# v0_3.net
KiCad netlist of a schematic drawn in EAGLE
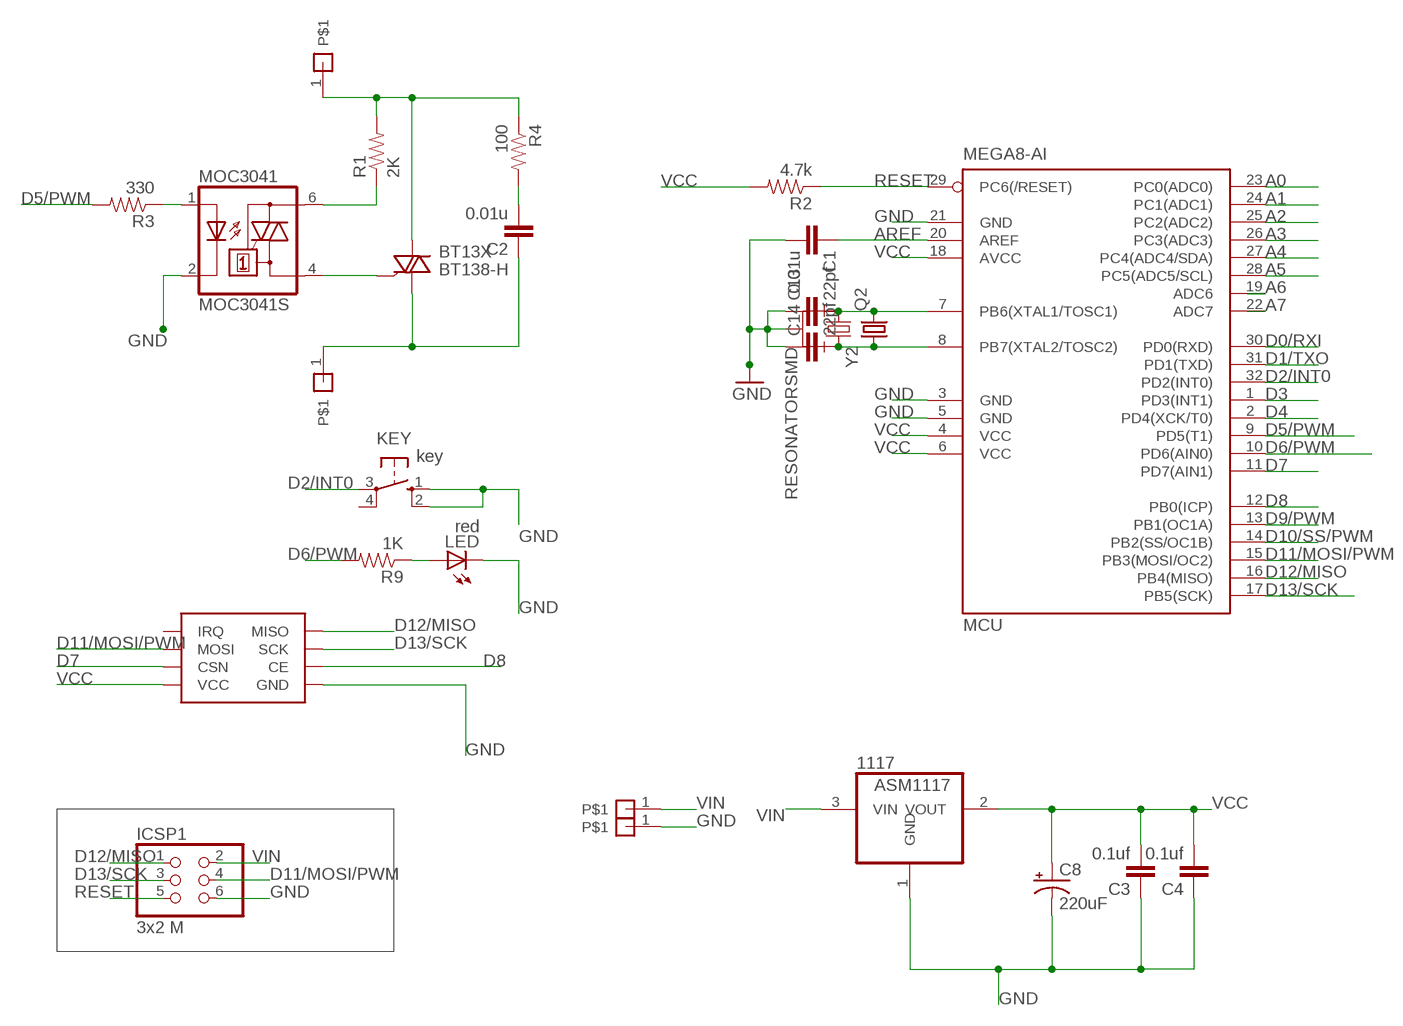
[diagram p0: schematic, sheet 1]

(export (version "E")
  (design (tool "Eeschema 10.0.6"))
  (components
    (comp (ref "1117")
      (value "ASM1117")
      (footprint "eagle-import:SOT223")
      (fields (field (name "MPN") "REG1117"))
      (libsource (lib "eagle-import") (part "REG1117"))
    )
    (comp (ref "BT13X")
      (value "BT138-H")
      (footprint "eagle-import:TO220BH")
      (libsource (lib "eagle-import") (part "BT138-H"))
    )
    (comp (ref "C1")
      (value "0.01u")
      (footprint "eagle-import:0603-CAP")
      (libsource (lib "eagle-import") (part "MY2_CAP0603-CAP"))
    )
    (comp (ref "C2")
      (value "0.01u")
      (footprint "eagle-import:C050-024X044")
      (libsource (lib "eagle-import") (part "C-EU050-024X044"))
    )
    (comp (ref "C3")
      (value "0.1uf")
      (footprint "eagle-import:0603-CAP")
      (libsource (lib "eagle-import") (part "MY_CAP0603-CAP"))
    )
    (comp (ref "C4")
      (value "0.1uf")
      (footprint "eagle-import:0603-CAP")
      (libsource (lib "eagle-import") (part "MY_CAP0603-CAP"))
    )
    (comp (ref "C8")
      (value "220uF")
      (footprint "eagle-import:EIA3528")
      (libsource (lib "eagle-import") (part "CAP_POL3528"))
    )
    (comp (ref "C13")
      (value "22pf")
      (footprint "eagle-import:0603-CAP")
      (libsource (lib "eagle-import") (part "CAP0603-CAP"))
    )
    (comp (ref "C14")
      (value "22pf")
      (footprint "eagle-import:0603-CAP")
      (libsource (lib "eagle-import") (part "CAP0603-CAP"))
    )
    (comp (ref "ICSP1")
      (value "3x2 M")
      (footprint "eagle-import:2X03")
      (libsource (lib "eagle-import") (part "PINHD-2X3"))
    )
    (comp (ref "KEY")
      (value "key")
      (footprint "eagle-import:B3F-10XX")
      (fields
        (field (name "MPN") "B3F-1000")
        (field (name "MPN_1") "B3F-1000")
        (field (name "OC_FARNELL") "176432")
        (field (name "OC_NEWARK") "36M3542")
      )
      (libsource (lib "eagle-import") (part "10-XX"))
    )
    (comp (ref "LED")
      (value "red")
      (footprint "eagle-import:LED3MM")
      (libsource (lib "eagle-import") (part "LED3MM"))
    )
    (comp (ref "MCU")
      (value "MEGA8-AI")
      (footprint "eagle-import:TQFP32-08")
      (fields (field (name "MPN") "ATMEGA8-16AU"))
      (libsource (lib "eagle-import") (part "MEGA8-AI"))
    )
    (comp (ref "MOC3041")
      (value "MOC3041S")
      (footprint "eagle-import:DIL6-SMD")
      (fields
        (field (name "MF") "FAIRCHILD SEMICONDUCTOR")
        (field (name "MPN") "MOC3041S-M")
        (field (name "MF_1") "FAIRCHILD SEMICONDUCTOR")
        (field (name "MPN_1") "MOC3041S-M")
        (field (name "OC_NEWARK") "05C2885")
      )
      (libsource (lib "eagle-import") (part "MOC30S41"))
    )
    (comp (ref "Q2")
      (value "CRYSTALHC49S")
      (footprint "eagle-import:HC49_S")
      (libsource (lib "eagle-import") (part "CRYSTALHC49S"))
    )
    (comp (ref "R1")
      (value "2K")
      (footprint "eagle-import:1206")
      (libsource (lib "eagle-import") (part "MY3_RESISTOR1206"))
    )
    (comp (ref "R2")
      (value "4.7k")
      (footprint "eagle-import:0603-RES")
      (libsource (lib "eagle-import") (part "RESISTOR0603-RES"))
    )
    (comp (ref "R3")
      (value "330")
      (footprint "eagle-import:0603-RES")
      (libsource (lib "eagle-import") (part "RESISTOR0603-RES"))
    )
    (comp (ref "R4")
      (value "100")
      (footprint "eagle-import:1206")
      (libsource (lib "eagle-import") (part "MY3_RESISTOR1206"))
    )
    (comp (ref "R9")
      (value "1K")
      (footprint "eagle-import:0603-RES")
      (libsource (lib "eagle-import") (part "RESISTOR0603-RES"))
    )
    (comp (ref "U$1")
      (value "PIN1")
      (footprint "eagle-import:PIN1")
      (libsource (lib "eagle-import") (part "PIN1"))
    )
    (comp (ref "U$2")
      (value "PIN1")
      (footprint "eagle-import:PIN1")
      (libsource (lib "eagle-import") (part "PIN1"))
    )
    (comp (ref "U$3")
      (value "PIN1")
      (footprint "eagle-import:PIN1")
      (libsource (lib "eagle-import") (part "PIN1"))
    )
    (comp (ref "U$4")
      (value "PIN1")
      (footprint "eagle-import:PIN1")
      (libsource (lib "eagle-import") (part "PIN1"))
    )
    (comp (ref "U$6")
      (value "NRF")
      (footprint "eagle-import:NRF")
      (libsource (lib "eagle-import") (part "NRF"))
    )
    (comp (ref "Y2")
      (value "RESONATORSMD")
      (footprint "eagle-import:RESONATOR-SMD")
      (libsource (lib "eagle-import") (part "RESONATORSMD"))
    )
  )
  (nets
    (net (code "1") (name "/A0") (class "Default")
      (node (ref "MCU") (pin "23") (pinfunction "PC0(ADC0)_23") (pintype "bidirectional"))
    )
    (net (code "2") (name "/A1") (class "Default")
      (node (ref "MCU") (pin "24") (pinfunction "PC1(ADC1)_24") (pintype "bidirectional"))
    )
    (net (code "3") (name "/A2") (class "Default")
      (node (ref "MCU") (pin "25") (pinfunction "PC2(ADC2)_25") (pintype "bidirectional"))
    )
    (net (code "4") (name "/A3") (class "Default")
      (node (ref "MCU") (pin "26") (pinfunction "PC3(ADC3)_26") (pintype "bidirectional"))
    )
    (net (code "5") (name "/A4") (class "Default")
      (node (ref "MCU") (pin "27") (pinfunction "PC4(ADC4/SDA)_27") (pintype "bidirectional"))
    )
    (net (code "6") (name "/A5") (class "Default")
      (node (ref "MCU") (pin "28") (pinfunction "PC5(ADC5/SCL)_28") (pintype "bidirectional"))
    )
    (net (code "7") (name "/A6") (class "Default")
      (node (ref "MCU") (pin "19") (pinfunction "ADC6_19") (pintype "bidirectional"))
    )
    (net (code "8") (name "/A7") (class "Default")
      (node (ref "MCU") (pin "22") (pinfunction "ADC7_22") (pintype "bidirectional"))
    )
    (net (code "9") (name "/AREF") (class "Default")
      (node (ref "C1") (pin "1") (pinfunction "1_1") (pintype "passive"))
      (node (ref "MCU") (pin "20") (pinfunction "AREF_20") (pintype "passive"))
    )
    (net (code "10") (name "/D0{slash}RXI") (class "Default")
      (node (ref "MCU") (pin "30") (pinfunction "PD0(RXD)_30") (pintype "bidirectional"))
    )
    (net (code "11") (name "/D1{slash}TXO") (class "Default")
      (node (ref "MCU") (pin "31") (pinfunction "PD1(TXD)_31") (pintype "bidirectional"))
    )
    (net (code "12") (name "/D2{slash}INT0") (class "Default")
      (node (ref "KEY") (pin "3") (pinfunction "P_3") (pintype "passive"))
      (node (ref "MCU") (pin "32") (pinfunction "PD2(INT0)_32") (pintype "bidirectional"))
    )
    (net (code "13") (name "/D3") (class "Default")
      (node (ref "MCU") (pin "1") (pinfunction "PD3(INT1)_1") (pintype "bidirectional"))
    )
    (net (code "14") (name "/D4") (class "Default")
      (node (ref "MCU") (pin "2") (pinfunction "PD4(XCK/T0)_2") (pintype "bidirectional"))
    )
    (net (code "15") (name "/D5{slash}PWM") (class "Default")
      (node (ref "MCU") (pin "9") (pinfunction "PD5(T1)_9") (pintype "bidirectional"))
      (node (ref "R3") (pin "2") (pinfunction "2_2") (pintype "passive"))
    )
    (net (code "16") (name "/D6{slash}PWM") (class "Default")
      (node (ref "MCU") (pin "10") (pinfunction "PD6(AIN0)_10") (pintype "bidirectional"))
      (node (ref "R9") (pin "2") (pinfunction "2_2") (pintype "passive"))
    )
    (net (code "17") (name "/D7") (class "Default")
      (node (ref "MCU") (pin "11") (pinfunction "PD7(AIN1)_11") (pintype "bidirectional"))
      (node (ref "U$6") (pin "P$4") (pinfunction "CSN_P$4") (pintype "bidirectional"))
    )
    (net (code "18") (name "/D8") (class "Default")
      (node (ref "MCU") (pin "12") (pinfunction "PB0(ICP)_12") (pintype "bidirectional"))
      (node (ref "U$6") (pin "P$3") (pinfunction "CE_P$3") (pintype "bidirectional"))
    )
    (net (code "19") (name "/D9{slash}PWM") (class "Default")
      (node (ref "MCU") (pin "13") (pinfunction "PB1(OC1A)_13") (pintype "bidirectional"))
    )
    (net (code "20") (name "/D10{slash}SS{slash}PWM") (class "Default")
      (node (ref "MCU") (pin "14") (pinfunction "PB2(SS/OC1B)_14") (pintype "bidirectional"))
    )
    (net (code "21") (name "/D11{slash}MOSI{slash}PWM") (class "Default")
      (node (ref "ICSP1") (pin "4") (pinfunction "4_4") (pintype "passive"))
      (node (ref "MCU") (pin "15") (pinfunction "PB3(MOSI/OC2)_15") (pintype "bidirectional"))
      (node (ref "U$6") (pin "P$6") (pinfunction "MOSI_P$6") (pintype "bidirectional"))
    )
    (net (code "22") (name "/D12{slash}MISO") (class "Default")
      (node (ref "ICSP1") (pin "1") (pinfunction "1_1") (pintype "passive"))
      (node (ref "MCU") (pin "16") (pinfunction "PB4(MISO)_16") (pintype "bidirectional"))
      (node (ref "U$6") (pin "P$7") (pinfunction "MISO_P$7") (pintype "bidirectional"))
    )
    (net (code "23") (name "/D13{slash}SCK") (class "Default")
      (node (ref "ICSP1") (pin "3") (pinfunction "3_3") (pintype "passive"))
      (node (ref "MCU") (pin "17") (pinfunction "PB5(SCK)_17") (pintype "bidirectional"))
      (node (ref "U$6") (pin "P$5") (pinfunction "SCK_P$5") (pintype "bidirectional"))
    )
    (net (code "24") (name "/RESET") (class "Default")
      (node (ref "ICSP1") (pin "5") (pinfunction "5_5") (pintype "passive"))
      (node (ref "MCU") (pin "29") (pinfunction "PC6(/RESET)_29") (pintype "bidirectional"))
      (node (ref "R2") (pin "1") (pinfunction "1_1") (pintype "passive"))
    )
    (net (code "25") (name "/VCC") (class "Default")
      (node (ref "1117") (pin "2") (pinfunction "VOUT_2") (pintype "output"))
      (node (ref "C3") (pin "2") (pinfunction "2_2") (pintype "passive"))
      (node (ref "C4") (pin "2") (pinfunction "2_2") (pintype "passive"))
      (node (ref "C8") (pin "A") (pinfunction "+_A") (pintype "passive"))
      (node (ref "MCU") (pin "18") (pinfunction "AVCC_18") (pintype "power_in"))
      (node (ref "MCU") (pin "4") (pinfunction "VCC_4") (pintype "power_in"))
      (node (ref "MCU") (pin "6") (pinfunction "VCC_6") (pintype "power_in"))
      (node (ref "R2") (pin "2") (pinfunction "2_2") (pintype "passive"))
      (node (ref "U$6") (pin "P$2") (pinfunction "VCC_P$2") (pintype "bidirectional"))
    )
    (net (code "26") (name "/VIN") (class "Default")
      (node (ref "1117") (pin "3") (pinfunction "VIN_3") (pintype "input"))
      (node (ref "ICSP1") (pin "2") (pinfunction "2_2") (pintype "passive"))
      (node (ref "U$3") (pin "1") (pinfunction "P$1_1") (pintype "bidirectional"))
    )
    (net (code "27") (name "GND") (class "Default")
      (node (ref "1117") (pin "1") (pinfunction "GND_1") (pintype "power_in"))
      (node (ref "C1") (pin "2") (pinfunction "2_2") (pintype "passive"))
      (node (ref "C13") (pin "1") (pinfunction "1_1") (pintype "passive"))
      (node (ref "C14") (pin "1") (pinfunction "1_1") (pintype "passive"))
      (node (ref "C3") (pin "1") (pinfunction "1_1") (pintype "passive"))
      (node (ref "C4") (pin "1") (pinfunction "1_1") (pintype "passive"))
      (node (ref "C8") (pin "C") (pinfunction "-_C") (pintype "passive"))
      (node (ref "ICSP1") (pin "6") (pinfunction "6_6") (pintype "passive"))
      (node (ref "KEY") (pin "1") (pinfunction "S_1") (pintype "passive"))
      (node (ref "KEY") (pin "2") (pinfunction "S1_2") (pintype "passive"))
      (node (ref "LED") (pin "K") (pinfunction "C_K") (pintype "passive"))
      (node (ref "MCU") (pin "21") (pinfunction "GND_21") (pintype "power_in"))
      (node (ref "MCU") (pin "3") (pinfunction "GND_3") (pintype "power_in"))
      (node (ref "MCU") (pin "5") (pinfunction "GND_5") (pintype "power_in"))
      (node (ref "MOC3041") (pin "2") (pinfunction "C_2") (pintype "passive"))
      (node (ref "U$4") (pin "1") (pinfunction "P$1_1") (pintype "bidirectional"))
      (node (ref "U$6") (pin "P$1") (pinfunction "GND_P$1") (pintype "bidirectional"))
      (node (ref "Y2") (pin "2") (pinfunction "2_2") (pintype "passive"))
    )
    (net (code "28") (name "Net-(BT13X-A1)") (class "Default")
      (node (ref "BT13X") (pin "T1") (pinfunction "A1_T1") (pintype "passive"))
      (node (ref "C2") (pin "1") (pinfunction "1_1") (pintype "passive"))
      (node (ref "U$1") (pin "1") (pinfunction "P$1_1") (pintype "bidirectional"))
    )
    (net (code "29") (name "Net-(BT13X-A2)") (class "Default")
      (node (ref "BT13X") (pin "T2") (pinfunction "A2_T2") (pintype "passive"))
      (node (ref "R1") (pin "2") (pinfunction "2_2") (pintype "passive"))
      (node (ref "R4") (pin "1") (pinfunction "1_1") (pintype "passive"))
      (node (ref "U$2") (pin "1") (pinfunction "P$1_1") (pintype "bidirectional"))
    )
    (net (code "30") (name "Net-(C2-Pad2)") (class "Default")
      (node (ref "C2") (pin "2") (pinfunction "2_2") (pintype "passive"))
      (node (ref "R4") (pin "2") (pinfunction "2_2") (pintype "passive"))
    )
    (net (code "31") (name "Net-(LED-PadA)") (class "Default")
      (node (ref "LED") (pin "A") (pinfunction "A_A") (pintype "passive"))
      (node (ref "R9") (pin "1") (pinfunction "1_1") (pintype "passive"))
    )
    (net (code "32") (name "Net-(MCU-PB6(XTAL1{slash}TOSC1))") (class "Default")
      (node (ref "C13") (pin "2") (pinfunction "2_2") (pintype "passive"))
      (node (ref "MCU") (pin "7") (pinfunction "PB6(XTAL1/TOSC1)_7") (pintype "bidirectional"))
      (node (ref "Q2") (pin "2") (pinfunction "2_2") (pintype "passive"))
      (node (ref "Y2") (pin "1") (pinfunction "1_1") (pintype "passive"))
    )
    (net (code "33") (name "Net-(MCU-PB7(XTAL2{slash}TOSC2))") (class "Default")
      (node (ref "C14") (pin "2") (pinfunction "2_2") (pintype "passive"))
      (node (ref "MCU") (pin "8") (pinfunction "PB7(XTAL2/TOSC2)_8") (pintype "bidirectional"))
      (node (ref "Q2") (pin "1") (pinfunction "1_1") (pintype "passive"))
      (node (ref "Y2") (pin "3") (pinfunction "3_3") (pintype "passive"))
    )
    (net (code "34") (name "Net-(MOC3041-A)") (class "Default")
      (node (ref "MOC3041") (pin "1") (pinfunction "A_1") (pintype "passive"))
      (node (ref "R3") (pin "1") (pinfunction "1_1") (pintype "passive"))
    )
    (net (code "35") (name "Net-(MOC3041-A1)") (class "Default")
      (node (ref "BT13X") (pin "G") (pinfunction "G_G") (pintype "passive"))
      (node (ref "MOC3041") (pin "4") (pinfunction "A1_4") (pintype "passive"))
    )
    (net (code "36") (name "Net-(MOC3041-A2)") (class "Default")
      (node (ref "MOC3041") (pin "6") (pinfunction "A2_6") (pintype "passive"))
      (node (ref "R1") (pin "1") (pinfunction "1_1") (pintype "passive"))
    )
    (net (code "37") (name "unconnected-(KEY-P1-Pad4)") (class "Default")
      (node (ref "KEY") (pin "4") (pinfunction "P1_4") (pintype "passive"))
    )
    (net (code "38") (name "unconnected-(U$6-IRQ-PadP$8)") (class "Default")
      (node (ref "U$6") (pin "P$8") (pinfunction "IRQ_P$8") (pintype "bidirectional"))
    )
  )
)
